# Arduino-Pro-Mini-v11.net
KiCad netlist of a schematic drawn in EAGLE
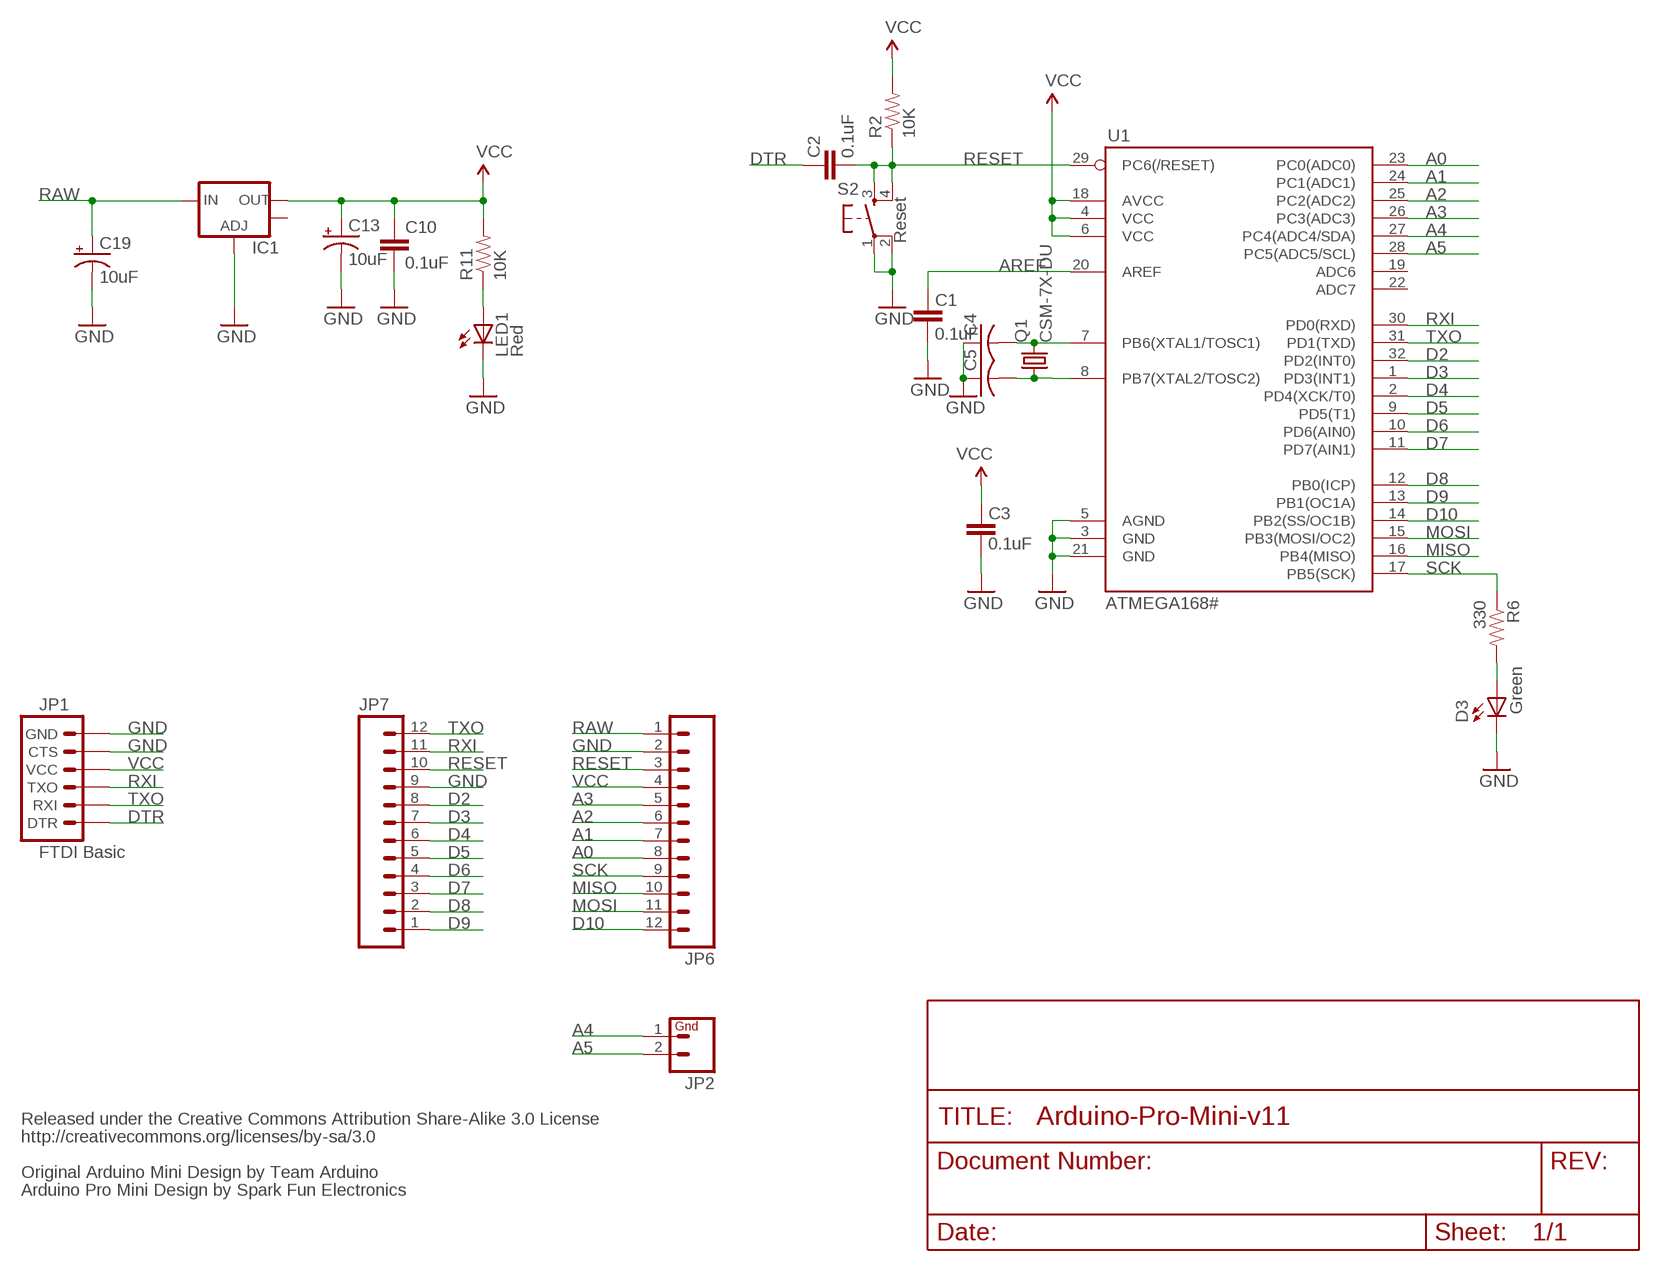
[diagram p0: schematic, sheet 1]

(export (version "E")
  (design (tool "Eeschema 10.0.6"))
  (components
    (comp (ref "C1")
      (value "0.1uF")
      (footprint "eagle-import:0805")
      (libsource (lib "eagle-import") (part "CAP0805"))
    )
    (comp (ref "C2")
      (value "0.1uF")
      (footprint "eagle-import:0805")
      (libsource (lib "eagle-import") (part "CAP0805"))
    )
    (comp (ref "C3")
      (value "0.1uF")
      (footprint "eagle-import:0805")
      (libsource (lib "eagle-import") (part "CAP0805"))
    )
    (comp (ref "C4")
      (value "C-USC0805")
      (footprint "eagle-import:C0805")
      (libsource (lib "eagle-import") (part "C-USC0805"))
    )
    (comp (ref "C5")
      (value "C-USC0805")
      (footprint "eagle-import:C0805")
      (libsource (lib "eagle-import") (part "C-USC0805"))
    )
    (comp (ref "C10")
      (value "0.1uF")
      (footprint "eagle-import:0805")
      (libsource (lib "eagle-import") (part "CAP0805"))
    )
    (comp (ref "C13")
      (value "10uF")
      (footprint "eagle-import:EIA3216")
      (libsource (lib "eagle-import") (part "CAP_POL1206"))
    )
    (comp (ref "C19")
      (value "10uF")
      (footprint "eagle-import:EIA3216")
      (libsource (lib "eagle-import") (part "CAP_POL1206"))
    )
    (comp (ref "D3")
      (value "Green")
      (footprint "eagle-import:LED-0603")
      (libsource (lib "eagle-import") (part "LED0603"))
    )
    (comp (ref "IC1")
      (value "V_REG_LM1117SOT223")
      (footprint "eagle-import:SOT223")
      (libsource (lib "eagle-import") (part "V_REG_LM1117SOT223"))
    )
    (comp (ref "JP1")
      (value "FTDI Basic")
      (footprint "eagle-import:1X06")
      (libsource (lib "eagle-import") (part "ARDUINO_SERIAL_PROGRAMPTH"))
    )
    (comp (ref "JP2")
      (value "M02PTH")
      (footprint "eagle-import:1X02")
      (libsource (lib "eagle-import") (part "M02PTH"))
    )
    (comp (ref "JP6")
      (value "M12PTH")
      (footprint "eagle-import:1X12")
      (libsource (lib "eagle-import") (part "M12PTH"))
    )
    (comp (ref "JP7")
      (value "M12PTH")
      (footprint "eagle-import:1X12")
      (libsource (lib "eagle-import") (part "M12PTH"))
    )
    (comp (ref "LED1")
      (value "Red")
      (footprint "eagle-import:LED-0603")
      (libsource (lib "eagle-import") (part "LED0603"))
    )
    (comp (ref "Q1")
      (value "CSM-7X-DU")
      (footprint "eagle-import:CSM-7X-DU")
      (libsource (lib "eagle-import") (part "CSM-7X-DU"))
    )
    (comp (ref "R2")
      (value "10K")
      (footprint "eagle-import:0805")
      (libsource (lib "eagle-import") (part "RESISTOR"))
    )
    (comp (ref "R6")
      (value "330")
      (footprint "eagle-import:0805")
      (libsource (lib "eagle-import") (part "RESISTOR"))
    )
    (comp (ref "R11")
      (value "10K")
      (footprint "eagle-import:0805")
      (libsource (lib "eagle-import") (part "RESISTOR"))
    )
    (comp (ref "S2")
      (value "Reset")
      (footprint "eagle-import:TACTILE_SWITCH_SMD")
      (libsource (lib "eagle-import") (part "TAC_SWITCHSND"))
    )
    (comp (ref "U1")
      (value "ATMEGA168#")
      (footprint "eagle-import:TQFP32-08")
      (libsource (lib "eagle-import") (part "ATMEGA168"))
    )
  )
  (nets
    (net (code "1") (name "/A0") (class "Default")
      (node (ref "JP6") (pin "8") (pinfunction "8_8") (pintype "passive"))
      (node (ref "U1") (pin "23") (pinfunction "PC0(ADC0)_23") (pintype "bidirectional"))
    )
    (net (code "2") (name "/A1") (class "Default")
      (node (ref "JP6") (pin "7") (pinfunction "7_7") (pintype "passive"))
      (node (ref "U1") (pin "24") (pinfunction "PC1(ADC1)_24") (pintype "bidirectional"))
    )
    (net (code "3") (name "/A2") (class "Default")
      (node (ref "JP6") (pin "6") (pinfunction "6_6") (pintype "passive"))
      (node (ref "U1") (pin "25") (pinfunction "PC2(ADC2)_25") (pintype "bidirectional"))
    )
    (net (code "4") (name "/A3") (class "Default")
      (node (ref "JP6") (pin "5") (pinfunction "5_5") (pintype "passive"))
      (node (ref "U1") (pin "26") (pinfunction "PC3(ADC3)_26") (pintype "bidirectional"))
    )
    (net (code "5") (name "/A4") (class "Default")
      (node (ref "JP2") (pin "1") (pinfunction "1_1") (pintype "passive"))
      (node (ref "U1") (pin "27") (pinfunction "PC4(ADC4/SDA)_27") (pintype "bidirectional"))
    )
    (net (code "6") (name "/A5") (class "Default")
      (node (ref "JP2") (pin "2") (pinfunction "2_2") (pintype "passive"))
      (node (ref "U1") (pin "28") (pinfunction "PC5(ADC5/SCL)_28") (pintype "bidirectional"))
    )
    (net (code "7") (name "/AREF") (class "Default")
      (node (ref "C1") (pin "2") (pinfunction "2_2") (pintype "passive"))
      (node (ref "U1") (pin "20") (pinfunction "AREF_20") (pintype "bidirectional"))
    )
    (net (code "8") (name "/D2") (class "Default")
      (node (ref "JP7") (pin "8") (pinfunction "8_8") (pintype "passive"))
      (node (ref "U1") (pin "32") (pinfunction "PD2(INT0)_32") (pintype "bidirectional"))
    )
    (net (code "9") (name "/D3") (class "Default")
      (node (ref "JP7") (pin "7") (pinfunction "7_7") (pintype "passive"))
      (node (ref "U1") (pin "1") (pinfunction "PD3(INT1)_1") (pintype "bidirectional"))
    )
    (net (code "10") (name "/D4") (class "Default")
      (node (ref "JP7") (pin "6") (pinfunction "6_6") (pintype "passive"))
      (node (ref "U1") (pin "2") (pinfunction "PD4(XCK/T0)_2") (pintype "bidirectional"))
    )
    (net (code "11") (name "/D5") (class "Default")
      (node (ref "JP7") (pin "5") (pinfunction "5_5") (pintype "passive"))
      (node (ref "U1") (pin "9") (pinfunction "PD5(T1)_9") (pintype "bidirectional"))
    )
    (net (code "12") (name "/D6") (class "Default")
      (node (ref "JP7") (pin "4") (pinfunction "4_4") (pintype "passive"))
      (node (ref "U1") (pin "10") (pinfunction "PD6(AIN0)_10") (pintype "bidirectional"))
    )
    (net (code "13") (name "/D7") (class "Default")
      (node (ref "JP7") (pin "3") (pinfunction "3_3") (pintype "passive"))
      (node (ref "U1") (pin "11") (pinfunction "PD7(AIN1)_11") (pintype "bidirectional"))
    )
    (net (code "14") (name "/D8") (class "Default")
      (node (ref "JP7") (pin "2") (pinfunction "2_2") (pintype "passive"))
      (node (ref "U1") (pin "12") (pinfunction "PB0(ICP)_12") (pintype "bidirectional"))
    )
    (net (code "15") (name "/D9") (class "Default")
      (node (ref "JP7") (pin "1") (pinfunction "1_1") (pintype "passive"))
      (node (ref "U1") (pin "13") (pinfunction "PB1(OC1A)_13") (pintype "bidirectional"))
    )
    (net (code "16") (name "/D10") (class "Default")
      (node (ref "JP6") (pin "12") (pinfunction "12_12") (pintype "passive"))
      (node (ref "U1") (pin "14") (pinfunction "PB2(SS/OC1B)_14") (pintype "bidirectional"))
    )
    (net (code "17") (name "/DTR") (class "Default")
      (node (ref "C2") (pin "2") (pinfunction "2_2") (pintype "passive"))
      (node (ref "JP1") (pin "1") (pinfunction "DTR_1") (pintype "passive"))
    )
    (net (code "18") (name "/MISO") (class "Default")
      (node (ref "JP6") (pin "10") (pinfunction "10_10") (pintype "passive"))
      (node (ref "U1") (pin "16") (pinfunction "PB4(MISO)_16") (pintype "bidirectional"))
    )
    (net (code "19") (name "/MOSI") (class "Default")
      (node (ref "JP6") (pin "11") (pinfunction "11_11") (pintype "passive"))
      (node (ref "U1") (pin "15") (pinfunction "PB3(MOSI/OC2)_15") (pintype "bidirectional"))
    )
    (net (code "20") (name "/RAW") (class "Default")
      (node (ref "C19") (pin "A") (pinfunction "+_A") (pintype "passive"))
      (node (ref "IC1") (pin "3") (pinfunction "IN_3") (pintype "input"))
      (node (ref "JP6") (pin "1") (pinfunction "1_1") (pintype "passive"))
    )
    (net (code "21") (name "/RESET") (class "Default")
      (node (ref "C2") (pin "1") (pinfunction "1_1") (pintype "passive"))
      (node (ref "JP6") (pin "3") (pinfunction "3_3") (pintype "passive"))
      (node (ref "JP7") (pin "10") (pinfunction "10_10") (pintype "passive"))
      (node (ref "R2") (pin "1") (pinfunction "1_1") (pintype "passive"))
      (node (ref "S2") (pin "3") (pinfunction "3_3") (pintype "passive"))
      (node (ref "S2") (pin "4") (pinfunction "4_4") (pintype "passive"))
      (node (ref "U1") (pin "29") (pinfunction "PC6(/RESET)_29") (pintype "bidirectional"))
    )
    (net (code "22") (name "/RXI") (class "Default")
      (node (ref "JP1") (pin "3") (pinfunction "TXO_3") (pintype "passive"))
      (node (ref "JP7") (pin "11") (pinfunction "11_11") (pintype "passive"))
      (node (ref "U1") (pin "30") (pinfunction "PD0(RXD)_30") (pintype "bidirectional"))
    )
    (net (code "23") (name "/SCK") (class "Default")
      (node (ref "JP6") (pin "9") (pinfunction "9_9") (pintype "passive"))
      (node (ref "R6") (pin "1") (pinfunction "1_1") (pintype "passive"))
      (node (ref "U1") (pin "17") (pinfunction "PB5(SCK)_17") (pintype "bidirectional"))
    )
    (net (code "24") (name "/TXO") (class "Default")
      (node (ref "JP1") (pin "2") (pinfunction "RXI_2") (pintype "passive"))
      (node (ref "JP7") (pin "12") (pinfunction "12_12") (pintype "passive"))
      (node (ref "U1") (pin "31") (pinfunction "PD1(TXD)_31") (pintype "bidirectional"))
    )
    (net (code "25") (name "GND") (class "Default")
      (node (ref "C1") (pin "1") (pinfunction "1_1") (pintype "passive"))
      (node (ref "C10") (pin "2") (pinfunction "2_2") (pintype "passive"))
      (node (ref "C13") (pin "C") (pinfunction "-_C") (pintype "passive"))
      (node (ref "C19") (pin "C") (pinfunction "-_C") (pintype "passive"))
      (node (ref "C3") (pin "1") (pinfunction "1_1") (pintype "passive"))
      (node (ref "C4") (pin "1") (pinfunction "1_1") (pintype "passive"))
      (node (ref "C5") (pin "1") (pinfunction "1_1") (pintype "passive"))
      (node (ref "D3") (pin "C") (pinfunction "C_C") (pintype "passive"))
      (node (ref "IC1") (pin "1") (pinfunction "ADJ_1") (pintype "input"))
      (node (ref "JP1") (pin "5") (pinfunction "CTS_5") (pintype "passive"))
      (node (ref "JP1") (pin "6") (pinfunction "GND_6") (pintype "passive"))
      (node (ref "JP6") (pin "2") (pinfunction "2_2") (pintype "passive"))
      (node (ref "JP7") (pin "9") (pinfunction "9_9") (pintype "passive"))
      (node (ref "LED1") (pin "C") (pinfunction "C_C") (pintype "passive"))
      (node (ref "S2") (pin "1") (pinfunction "1_1") (pintype "passive"))
      (node (ref "S2") (pin "2") (pinfunction "2_2") (pintype "passive"))
      (node (ref "U1") (pin "21") (pinfunction "GND_21") (pintype "bidirectional"))
      (node (ref "U1") (pin "3") (pinfunction "GND_3") (pintype "bidirectional"))
      (node (ref "U1") (pin "5") (pinfunction "AGND_5") (pintype "bidirectional"))
    )
    (net (code "26") (name "Net-(D3-PadA)") (class "Default")
      (node (ref "D3") (pin "A") (pinfunction "A_A") (pintype "passive"))
      (node (ref "R6") (pin "2") (pinfunction "2_2") (pintype "passive"))
    )
    (net (code "27") (name "Net-(LED1-PadA)") (class "Default")
      (node (ref "LED1") (pin "A") (pinfunction "A_A") (pintype "passive"))
      (node (ref "R11") (pin "1") (pinfunction "1_1") (pintype "passive"))
    )
    (net (code "28") (name "Net-(U1-PB6(XTAL1{slash}TOSC1))") (class "Default")
      (node (ref "C4") (pin "2") (pinfunction "2_2") (pintype "passive"))
      (node (ref "Q1") (pin "2") (pinfunction "2_2") (pintype "passive"))
      (node (ref "U1") (pin "7") (pinfunction "PB6(XTAL1/TOSC1)_7") (pintype "bidirectional"))
    )
    (net (code "29") (name "Net-(U1-PB7(XTAL2{slash}TOSC2))") (class "Default")
      (node (ref "C5") (pin "2") (pinfunction "2_2") (pintype "passive"))
      (node (ref "Q1") (pin "1") (pinfunction "1_1") (pintype "passive"))
      (node (ref "U1") (pin "8") (pinfunction "PB7(XTAL2/TOSC2)_8") (pintype "bidirectional"))
    )
    (net (code "30") (name "VCC") (class "Default")
      (node (ref "C10") (pin "1") (pinfunction "1_1") (pintype "passive"))
      (node (ref "C13") (pin "A") (pinfunction "+_A") (pintype "passive"))
      (node (ref "C3") (pin "2") (pinfunction "2_2") (pintype "passive"))
      (node (ref "IC1") (pin "2") (pinfunction "OUT_2") (pintype "output"))
      (node (ref "JP1") (pin "4") (pinfunction "VCC_4") (pintype "passive"))
      (node (ref "JP6") (pin "4") (pinfunction "4_4") (pintype "passive"))
      (node (ref "R11") (pin "2") (pinfunction "2_2") (pintype "passive"))
      (node (ref "R2") (pin "2") (pinfunction "2_2") (pintype "passive"))
      (node (ref "U1") (pin "18") (pinfunction "AVCC_18") (pintype "bidirectional"))
      (node (ref "U1") (pin "4") (pinfunction "VCC_4") (pintype "bidirectional"))
      (node (ref "U1") (pin "6") (pinfunction "VCC_6") (pintype "bidirectional"))
    )
    (net (code "31") (name "unconnected-(IC1-OUT-Pad4)") (class "Default")
      (node (ref "IC1") (pin "4") (pinfunction "OUT_4") (pintype "output"))
    )
    (net (code "32") (name "unconnected-(U1-ADC6-Pad19)") (class "Default")
      (node (ref "U1") (pin "19") (pinfunction "ADC6_19") (pintype "bidirectional"))
    )
    (net (code "33") (name "unconnected-(U1-ADC7-Pad22)") (class "Default")
      (node (ref "U1") (pin "22") (pinfunction "ADC7_22") (pintype "bidirectional"))
    )
  )
)
